# Pi_Tracker1.net
KiCad netlist of a schematic drawn in EAGLE
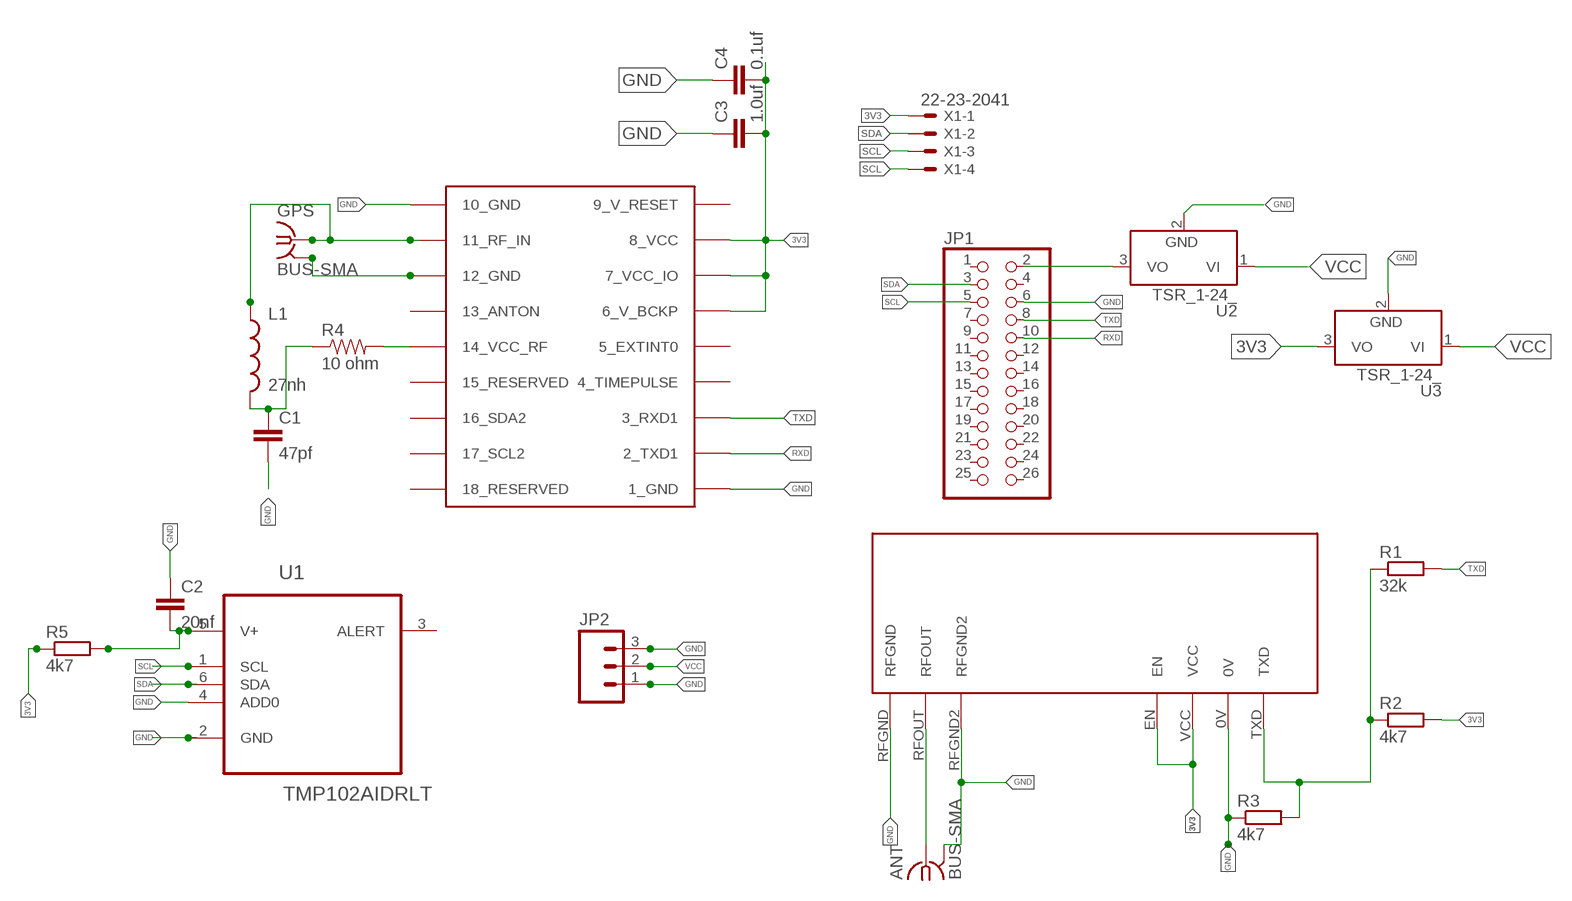
[diagram p0: schematic, sheet 1]

(export (version "E")
  (design (tool "Eeschema 10.0.6"))
  (components
    (comp (ref "ANT")
      (value "BUS-SMA")
      (footprint "eagle-import:BUS-SMA")
      (libsource (lib "eagle-import") (part "BUS-SMA"))
    )
    (comp (ref "C1")
      (value "47pf")
      (footprint "eagle-import:0603-CAP")
      (libsource (lib "eagle-import") (part "CAP0603-CAP"))
    )
    (comp (ref "C2")
      (value "20nf")
      (footprint "eagle-import:C0603")
      (libsource (lib "eagle-import") (part "C-EUC0603"))
    )
    (comp (ref "C3")
      (value "1.0uf")
      (footprint "eagle-import:C0603")
      (libsource (lib "eagle-import") (part "C-EUC0603"))
    )
    (comp (ref "C4")
      (value "0.1uf")
      (footprint "eagle-import:C0603")
      (libsource (lib "eagle-import") (part "C-EUC0603"))
    )
    (comp (ref "GPS")
      (value "BUS-SMA")
      (footprint "eagle-import:BUS-SMA")
      (libsource (lib "eagle-import") (part "BUS-SMA"))
    )
    (comp (ref "JP1")
      (value "PINHD-2X13")
      (footprint "eagle-import:2X13")
      (libsource (lib "eagle-import") (part "PINHD-2X13"))
    )
    (comp (ref "JP2")
      (value "M03PTH")
      (footprint "eagle-import:1X03")
      (libsource (lib "eagle-import") (part "M03PTH"))
    )
    (comp (ref "L1")
      (value "27nh")
      (footprint "eagle-import:0603")
      (libsource (lib "eagle-import") (part "INDUCTOR0603"))
    )
    (comp (ref "R1")
      (value "32k")
      (footprint "eagle-import:R0603")
      (libsource (lib "eagle-import") (part "R-EU_R0603"))
    )
    (comp (ref "R2")
      (value "4k7")
      (footprint "eagle-import:R0603")
      (libsource (lib "eagle-import") (part "R-EU_R0603"))
    )
    (comp (ref "R3")
      (value "4k7")
      (footprint "eagle-import:R0603")
      (libsource (lib "eagle-import") (part "R-EU_R0603"))
    )
    (comp (ref "R4")
      (value "10 ohm")
      (footprint "eagle-import:0603-RES")
      (libsource (lib "eagle-import") (part "RESISTOR0603"))
    )
    (comp (ref "R5")
      (value "4k7")
      (footprint "eagle-import:R0603")
      (libsource (lib "eagle-import") (part "R-EU_R0603"))
    )
    (comp (ref "U$1")
      (value "NTX2")
      (footprint "eagle-import:NTX2")
      (libsource (lib "eagle-import") (part "NTX2"))
    )
    (comp (ref "U$2")
      (value "UBLOX_MAX")
      (footprint "eagle-import:UBLOX_MAX")
      (libsource (lib "eagle-import") (part "UBLOX_MAX"))
    )
    (comp (ref "U1")
      (value "TMP102AIDRLT")
      (footprint "eagle-import:SOT50P160X60-6N")
      (libsource (lib "eagle-import") (part "TMP102AIDRLT"))
    )
    (comp (ref "U2")
      (value "TSR_1-24_")
      (footprint "eagle-import:TSR-1")
      (libsource (lib "eagle-import") (part "TSR_1-24_"))
    )
    (comp (ref "U3")
      (value "TSR_1-24_")
      (footprint "eagle-import:TSR-1")
      (libsource (lib "eagle-import") (part "TSR_1-24_"))
    )
    (comp (ref "X1")
      (value "22-23-2041")
      (footprint "eagle-import:22-23-2041")
      (fields (field (name "MF") "MOLEX"))
      (libsource (lib "eagle-import") (part "22-23-2041"))
    )
  )
  (nets
    (net (code "1") (name "/9_V_RESET") (class "Default")
      (node (ref "U$2") (pin "9_V_RESET") (pinfunction "9_V_RESET_9_V_RESET") (pintype "power_in"))
    )
    (net (code "2") (name "3V3") (class "Default")
      (node (ref "C2") (pin "2") (pinfunction "2_2") (pintype "passive"))
      (node (ref "C3") (pin "2") (pinfunction "2_2") (pintype "passive"))
      (node (ref "C4") (pin "2") (pinfunction "2_2") (pintype "passive"))
      (node (ref "R2") (pin "2") (pinfunction "2_2") (pintype "passive"))
      (node (ref "R5") (pin "1") (pinfunction "1_1") (pintype "passive"))
      (node (ref "R5") (pin "2") (pinfunction "2_2") (pintype "passive"))
      (node (ref "U$1") (pin "EN") (pinfunction "EN_EN") (pintype "bidirectional"))
      (node (ref "U$1") (pin "VCC") (pinfunction "VCC_VCC") (pintype "bidirectional"))
      (node (ref "U$2") (pin "6_V_BCKP") (pinfunction "6_V_BCKP_6_V_BCKP") (pintype "bidirectional"))
      (node (ref "U$2") (pin "7_VCC_IO") (pinfunction "7_VCC_IO_7_VCC_IO") (pintype "power_in"))
      (node (ref "U$2") (pin "8_VCC") (pinfunction "8_VCC_8_VCC") (pintype "power_in"))
      (node (ref "U1") (pin "5") (pinfunction "V+_5") (pintype "power_in"))
      (node (ref "U3") (pin "3") (pinfunction "VO_3") (pintype "power_in"))
      (node (ref "X1") (pin "1") (pinfunction "S_1") (pintype "passive"))
    )
    (net (code "3") (name "GND") (class "Default")
      (node (ref "ANT") (pin "2") (pinfunction "GND_2") (pintype "power_in"))
      (node (ref "ANT") (pin "3") (pinfunction "GND_3") (pintype "power_in"))
      (node (ref "ANT") (pin "4") (pinfunction "GND_4") (pintype "power_in"))
      (node (ref "ANT") (pin "5") (pinfunction "GND_5") (pintype "power_in"))
      (node (ref "C1") (pin "2") (pinfunction "2_2") (pintype "passive"))
      (node (ref "C2") (pin "1") (pinfunction "1_1") (pintype "passive"))
      (node (ref "C3") (pin "1") (pinfunction "1_1") (pintype "passive"))
      (node (ref "C4") (pin "1") (pinfunction "1_1") (pintype "passive"))
      (node (ref "GPS") (pin "2") (pinfunction "GND_2") (pintype "power_in"))
      (node (ref "GPS") (pin "3") (pinfunction "GND_3") (pintype "power_in"))
      (node (ref "GPS") (pin "4") (pinfunction "GND_4") (pintype "power_in"))
      (node (ref "GPS") (pin "5") (pinfunction "GND_5") (pintype "power_in"))
      (node (ref "JP1") (pin "6") (pinfunction "6_6") (pintype "passive"))
      (node (ref "JP2") (pin "1") (pinfunction "1_1") (pintype "passive"))
      (node (ref "JP2") (pin "3") (pinfunction "3_3") (pintype "passive"))
      (node (ref "R3") (pin "1") (pinfunction "1_1") (pintype "passive"))
      (node (ref "U$1") (pin "0V") (pinfunction "0V_0V") (pintype "bidirectional"))
      (node (ref "U$1") (pin "RFGND") (pinfunction "RFGND_RFGND") (pintype "bidirectional"))
      (node (ref "U$1") (pin "RFGND2") (pinfunction "RFGND2_RFGND2") (pintype "bidirectional"))
      (node (ref "U$2") (pin "10_GND") (pinfunction "10_GND_10_GND") (pintype "power_in"))
      (node (ref "U$2") (pin "12_GND") (pinfunction "12_GND_12_GND") (pintype "power_in"))
      (node (ref "U$2") (pin "1_GND") (pinfunction "1_GND_1_GND") (pintype "power_in"))
      (node (ref "U1") (pin "2") (pinfunction "GND_2") (pintype "passive"))
      (node (ref "U1") (pin "4") (pinfunction "ADD0_4") (pintype "input"))
      (node (ref "U2") (pin "2") (pinfunction "GND_2") (pintype "power_in"))
      (node (ref "U3") (pin "2") (pinfunction "GND_2") (pintype "power_in"))
      (node (ref "X1") (pin "4") (pinfunction "S_4") (pintype "passive"))
    )
    (net (code "4") (name "Net-(ANT-Pad1)") (class "Default")
      (node (ref "ANT") (pin "1") (pinfunction "1_1") (pintype "passive"))
      (node (ref "U$1") (pin "RFOUT") (pinfunction "RFOUT_RFOUT") (pintype "bidirectional"))
    )
    (net (code "5") (name "Net-(C1-Pad1)") (class "Default")
      (node (ref "C1") (pin "1") (pinfunction "1_1") (pintype "passive"))
      (node (ref "L1") (pin "2") (pinfunction "2_2") (pintype "passive"))
      (node (ref "R4") (pin "1") (pinfunction "1_1") (pintype "passive"))
    )
    (net (code "6") (name "Net-(GPS-Pad1)") (class "Default")
      (node (ref "GPS") (pin "1") (pinfunction "1_1") (pintype "passive"))
      (node (ref "L1") (pin "1") (pinfunction "1_1") (pintype "passive"))
      (node (ref "U$2") (pin "11_RF_IN") (pinfunction "11_RF_IN_11_RF_IN") (pintype "bidirectional"))
    )
    (net (code "7") (name "Net-(R1-Pad1)") (class "Default")
      (node (ref "R1") (pin "1") (pinfunction "1_1") (pintype "passive"))
      (node (ref "R2") (pin "1") (pinfunction "1_1") (pintype "passive"))
      (node (ref "R3") (pin "2") (pinfunction "2_2") (pintype "passive"))
      (node (ref "U$1") (pin "TXD") (pinfunction "TXD_TXD") (pintype "bidirectional"))
    )
    (net (code "8") (name "Net-(R4-Pad2)") (class "Default")
      (node (ref "R4") (pin "2") (pinfunction "2_2") (pintype "passive"))
      (node (ref "U$2") (pin "14_VCC_RF") (pinfunction "14_VCC_RF_14_VCC_RF") (pintype "bidirectional"))
    )
    (net (code "9") (name "Net-(U2-VO)") (class "Default")
      (node (ref "JP1") (pin "2") (pinfunction "2_2") (pintype "passive"))
      (node (ref "U2") (pin "3") (pinfunction "VO_3") (pintype "power_in"))
    )
    (net (code "10") (name "RXD") (class "Default")
      (node (ref "JP1") (pin "10") (pinfunction "10_10") (pintype "passive"))
      (node (ref "U$2") (pin "2_TXD1") (pinfunction "2_TXD1_2_TXD1") (pintype "bidirectional"))
    )
    (net (code "11") (name "SCL") (class "Default")
      (node (ref "JP1") (pin "5") (pinfunction "5_5") (pintype "passive"))
      (node (ref "U1") (pin "1") (pinfunction "SCL_1") (pintype "bidirectional"))
      (node (ref "X1") (pin "3") (pinfunction "S_3") (pintype "passive"))
    )
    (net (code "12") (name "SDA") (class "Default")
      (node (ref "JP1") (pin "3") (pinfunction "3_3") (pintype "passive"))
      (node (ref "U1") (pin "6") (pinfunction "SDA_6") (pintype "bidirectional"))
      (node (ref "X1") (pin "2") (pinfunction "S_2") (pintype "passive"))
    )
    (net (code "13") (name "TXD") (class "Default")
      (node (ref "JP1") (pin "8") (pinfunction "8_8") (pintype "passive"))
      (node (ref "R1") (pin "2") (pinfunction "2_2") (pintype "passive"))
      (node (ref "U$2") (pin "3_RXD1") (pinfunction "3_RXD1_3_RXD1") (pintype "bidirectional"))
    )
    (net (code "14") (name "VCC") (class "Default")
      (node (ref "JP2") (pin "2") (pinfunction "2_2") (pintype "passive"))
      (node (ref "U2") (pin "1") (pinfunction "VI_1") (pintype "power_in"))
      (node (ref "U3") (pin "1") (pinfunction "VI_1") (pintype "power_in"))
    )
    (net (code "15") (name "unconnected-(JP1-Pad1)") (class "Default")
      (node (ref "JP1") (pin "1") (pinfunction "1_1") (pintype "passive"))
    )
    (net (code "16") (name "unconnected-(JP1-Pad4)") (class "Default")
      (node (ref "JP1") (pin "4") (pinfunction "4_4") (pintype "passive"))
    )
    (net (code "17") (name "unconnected-(JP1-Pad7)") (class "Default")
      (node (ref "JP1") (pin "7") (pinfunction "7_7") (pintype "passive"))
    )
    (net (code "18") (name "unconnected-(JP1-Pad9)") (class "Default")
      (node (ref "JP1") (pin "9") (pinfunction "9_9") (pintype "passive"))
    )
    (net (code "19") (name "unconnected-(JP1-Pad11)") (class "Default")
      (node (ref "JP1") (pin "11") (pinfunction "11_11") (pintype "passive"))
    )
    (net (code "20") (name "unconnected-(JP1-Pad12)") (class "Default")
      (node (ref "JP1") (pin "12") (pinfunction "12_12") (pintype "passive"))
    )
    (net (code "21") (name "unconnected-(JP1-Pad13)") (class "Default")
      (node (ref "JP1") (pin "13") (pinfunction "13_13") (pintype "passive"))
    )
    (net (code "22") (name "unconnected-(JP1-Pad14)") (class "Default")
      (node (ref "JP1") (pin "14") (pinfunction "14_14") (pintype "passive"))
    )
    (net (code "23") (name "unconnected-(JP1-Pad15)") (class "Default")
      (node (ref "JP1") (pin "15") (pinfunction "15_15") (pintype "passive"))
    )
    (net (code "24") (name "unconnected-(JP1-Pad16)") (class "Default")
      (node (ref "JP1") (pin "16") (pinfunction "16_16") (pintype "passive"))
    )
    (net (code "25") (name "unconnected-(JP1-Pad17)") (class "Default")
      (node (ref "JP1") (pin "17") (pinfunction "17_17") (pintype "passive"))
    )
    (net (code "26") (name "unconnected-(JP1-Pad18)") (class "Default")
      (node (ref "JP1") (pin "18") (pinfunction "18_18") (pintype "passive"))
    )
    (net (code "27") (name "unconnected-(JP1-Pad19)") (class "Default")
      (node (ref "JP1") (pin "19") (pinfunction "19_19") (pintype "passive"))
    )
    (net (code "28") (name "unconnected-(JP1-Pad20)") (class "Default")
      (node (ref "JP1") (pin "20") (pinfunction "20_20") (pintype "passive"))
    )
    (net (code "29") (name "unconnected-(JP1-Pad21)") (class "Default")
      (node (ref "JP1") (pin "21") (pinfunction "21_21") (pintype "passive"))
    )
    (net (code "30") (name "unconnected-(JP1-Pad22)") (class "Default")
      (node (ref "JP1") (pin "22") (pinfunction "22_22") (pintype "passive"))
    )
    (net (code "31") (name "unconnected-(JP1-Pad23)") (class "Default")
      (node (ref "JP1") (pin "23") (pinfunction "23_23") (pintype "passive"))
    )
    (net (code "32") (name "unconnected-(JP1-Pad24)") (class "Default")
      (node (ref "JP1") (pin "24") (pinfunction "24_24") (pintype "passive"))
    )
    (net (code "33") (name "unconnected-(JP1-Pad25)") (class "Default")
      (node (ref "JP1") (pin "25") (pinfunction "25_25") (pintype "passive"))
    )
    (net (code "34") (name "unconnected-(JP1-Pad26)") (class "Default")
      (node (ref "JP1") (pin "26") (pinfunction "26_26") (pintype "passive"))
    )
    (net (code "35") (name "unconnected-(U$2-Pad4_TIMEPULSE)") (class "Default")
      (node (ref "U$2") (pin "4_TIMEPULSE") (pinfunction "4_TIMEPULSE_4_TIMEPULSE") (pintype "bidirectional"))
    )
    (net (code "36") (name "unconnected-(U$2-Pad5_EXTINT0)") (class "Default")
      (node (ref "U$2") (pin "5_EXTINT0") (pinfunction "5_EXTINT0_5_EXTINT0") (pintype "bidirectional"))
    )
    (net (code "37") (name "unconnected-(U$2-Pad13_ANTON)") (class "Default")
      (node (ref "U$2") (pin "13_ANTON") (pinfunction "13_ANTON_13_ANTON") (pintype "bidirectional"))
    )
    (net (code "38") (name "unconnected-(U$2-Pad15_RESERVED)") (class "Default")
      (node (ref "U$2") (pin "15_RESERVED") (pinfunction "15_RESERVED_15_RESERVED") (pintype "bidirectional"))
    )
    (net (code "39") (name "unconnected-(U$2-Pad16_SDA2)") (class "Default")
      (node (ref "U$2") (pin "16_SDA2") (pinfunction "16_SDA2_16_SDA2") (pintype "bidirectional"))
    )
    (net (code "40") (name "unconnected-(U$2-Pad17_SCL2)") (class "Default")
      (node (ref "U$2") (pin "17_SCL2") (pinfunction "17_SCL2_17_SCL2") (pintype "bidirectional"))
    )
    (net (code "41") (name "unconnected-(U$2-Pad18_RESERVED)") (class "Default")
      (node (ref "U$2") (pin "18_RESERVED") (pinfunction "18_RESERVED_18_RESERVED") (pintype "bidirectional"))
    )
    (net (code "42") (name "unconnected-(U1-ALERT-Pad3)") (class "Default")
      (node (ref "U1") (pin "3") (pinfunction "ALERT_3") (pintype "output"))
    )
  )
)
